# Sheet1.net
KiCad netlist of a schematic drawn in Altium Designer
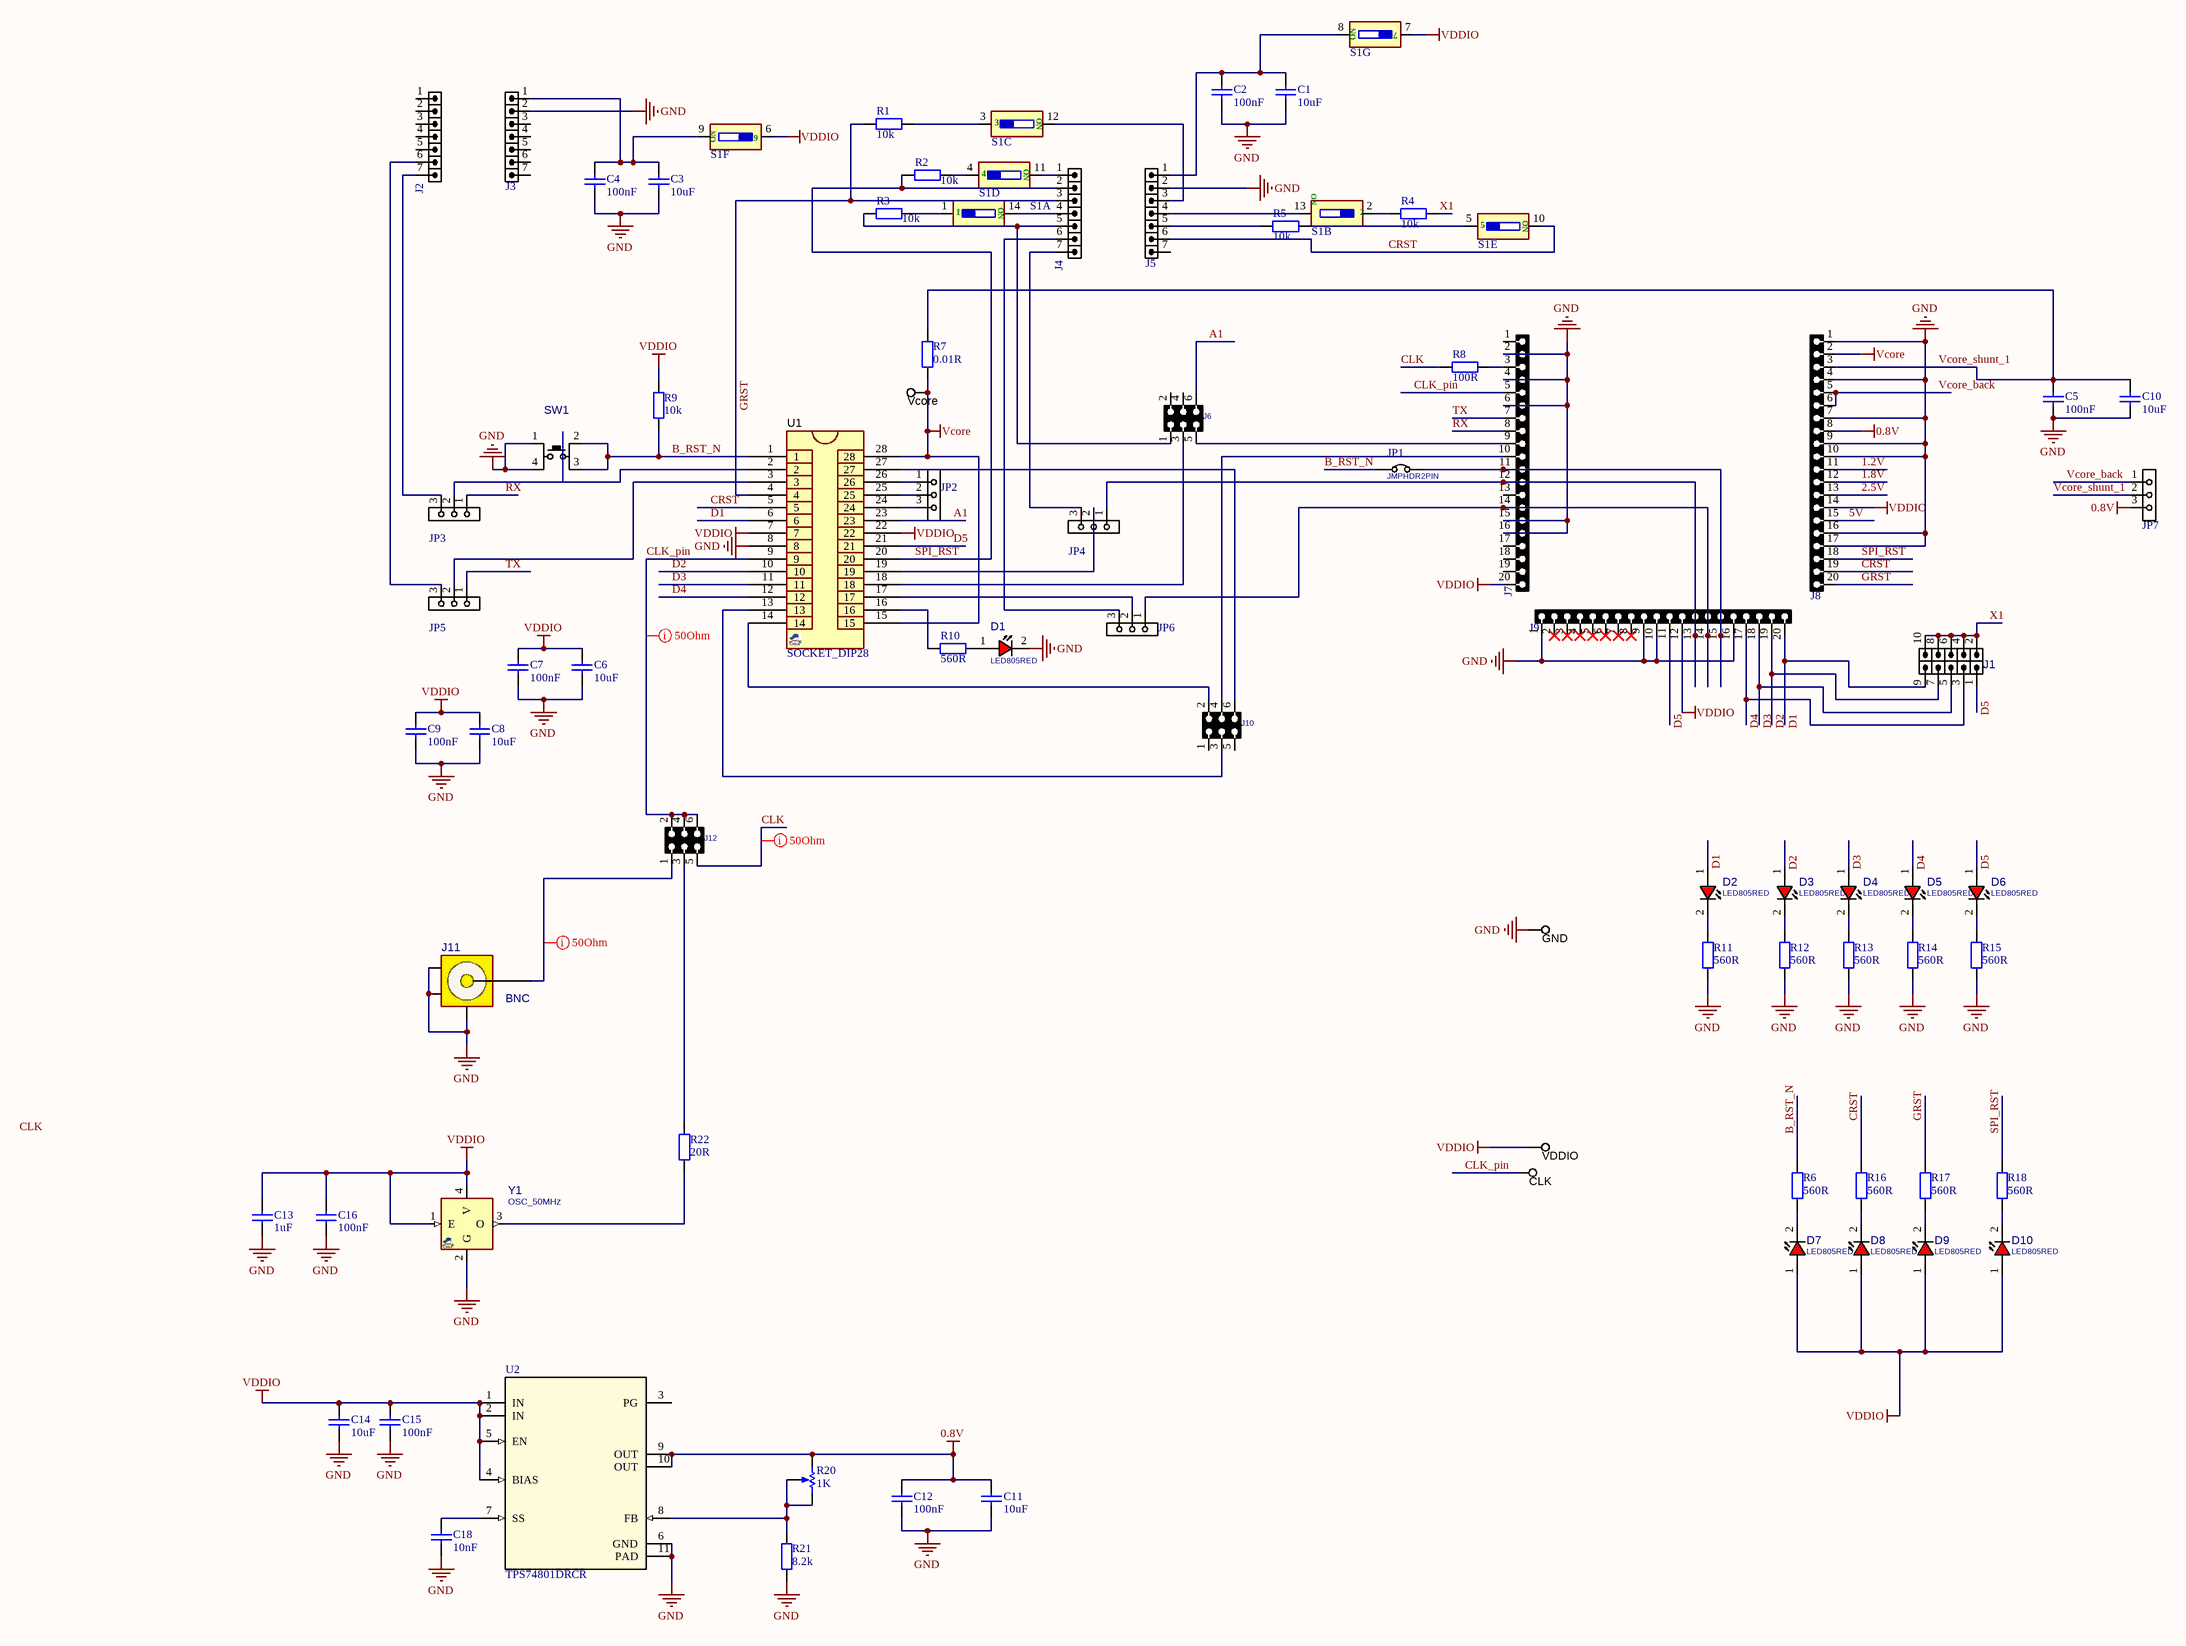
[diagram p0: Sheet1.SchDoc]

(export (version "E")
  (design (tool "Eeschema 10.0.6"))
  (components
    (comp (ref "C1")
      (value "10uF")
      (footprint "C1210")
      (description "smd capacitor 1206")
      (libsource (lib "mohamad_lib") (part "cap_SMD"))
    )
    (comp (ref "C2")
      (value "100nF")
      (footprint "C0805")
      (description "smd capacitor 1206")
      (libsource (lib "mohamad_lib") (part "cap_SMD"))
    )
    (comp (ref "C3")
      (value "10uF")
      (footprint "C1210")
      (description "smd capacitor 1206")
      (libsource (lib "mohamad_lib") (part "cap_SMD"))
    )
    (comp (ref "C4")
      (value "100nF")
      (footprint "C0805")
      (description "smd capacitor 1206")
      (libsource (lib "mohamad_lib") (part "cap_SMD"))
    )
    (comp (ref "C5")
      (value "100nF")
      (footprint "C0805")
      (description "smd capacitor 1206")
      (libsource (lib "mohamad_lib") (part "cap_SMD"))
    )
    (comp (ref "C6")
      (value "10uF")
      (footprint "C1210")
      (description "smd capacitor 1206")
      (libsource (lib "mohamad_lib") (part "cap_SMD"))
    )
    (comp (ref "C7")
      (value "100nF")
      (footprint "C0805")
      (description "smd capacitor 1206")
      (libsource (lib "mohamad_lib") (part "cap_SMD"))
    )
    (comp (ref "C8")
      (value "10uF")
      (footprint "C1210")
      (description "smd capacitor 1206")
      (libsource (lib "mohamad_lib") (part "cap_SMD"))
    )
    (comp (ref "C9")
      (value "100nF")
      (footprint "C0805")
      (description "smd capacitor 1206")
      (libsource (lib "mohamad_lib") (part "cap_SMD"))
    )
    (comp (ref "C10")
      (value "10uF")
      (footprint "C1210")
      (description "smd capacitor 1206")
      (libsource (lib "mohamad_lib") (part "cap_SMD"))
    )
    (comp (ref "C11")
      (value "10uF")
      (footprint "C1210")
      (description "smd capacitor 1206")
      (libsource (lib "mohamad_lib") (part "cap_SMD"))
    )
    (comp (ref "C12")
      (value "100nF")
      (footprint "C0805")
      (description "smd capacitor 1206")
      (libsource (lib "mohamad_lib") (part "cap_SMD"))
    )
    (comp (ref "C13")
      (value "1uF")
      (footprint "C0805")
      (description "smd capacitor 1206")
      (libsource (lib "mohamad_lib") (part "cap_SMD"))
    )
    (comp (ref "C14")
      (value "10uF")
      (footprint "C1210")
      (description "smd capacitor 1206")
      (libsource (lib "mohamad_lib") (part "cap_SMD"))
    )
    (comp (ref "C15")
      (value "100nF")
      (footprint "C0805")
      (description "smd capacitor 1206")
      (libsource (lib "mohamad_lib") (part "cap_SMD"))
    )
    (comp (ref "C16")
      (value "100nF")
      (footprint "C0805")
      (description "smd capacitor 1206")
      (libsource (lib "mohamad_lib") (part "cap_SMD"))
    )
    (comp (ref "C18")
      (value "10nF")
      (footprint "C0805")
      (description "smd capacitor 1206")
      (libsource (lib "mohamad_lib") (part "cap_SMD"))
    )
    (comp (ref "CLK")
      (value "TESTPOINT_BIG_BLK1")
      (footprint "TPTHD_C_BLK1")
      (description "TEST POINT")
      (fields (field (name "MANF") "MANF") (field (name "MANF_P#") "MANF_P#"))
      (libsource (lib "boorghani") (part "TESTPOINT_BIG_BLK1"))
    )
    (comp (ref "D1")
      (value "LED805RED")
      (footprint "LED0805RED")
      (description "LED, SMD, 0805, RED")
      (fields (field (name "MANF") "MANF") (field (name "MANF_P#") "MANF_PART#"))
      (libsource (lib "boorghani") (part "LED_SMD_0805_RED"))
    )
    (comp (ref "D2")
      (value "LED805RED")
      (footprint "LED0805RED")
      (description "LED, SMD, 0805, RED")
      (fields (field (name "MANF") "MANF") (field (name "MANF_P#") "MANF_PART#"))
      (libsource (lib "boorghani") (part "LED_SMD_0805_RED"))
    )
    (comp (ref "D3")
      (value "LED805RED")
      (footprint "LED0805RED")
      (description "LED, SMD, 0805, RED")
      (fields (field (name "MANF") "MANF") (field (name "MANF_P#") "MANF_PART#"))
      (libsource (lib "boorghani") (part "LED_SMD_0805_RED"))
    )
    (comp (ref "D4")
      (value "LED805RED")
      (footprint "LED0805RED")
      (description "LED, SMD, 0805, RED")
      (fields (field (name "MANF") "MANF") (field (name "MANF_P#") "MANF_PART#"))
      (libsource (lib "boorghani") (part "LED_SMD_0805_RED"))
    )
    (comp (ref "D5")
      (value "LED805RED")
      (footprint "LED0805RED")
      (description "LED, SMD, 0805, RED")
      (fields (field (name "MANF") "MANF") (field (name "MANF_P#") "MANF_PART#"))
      (libsource (lib "boorghani") (part "LED_SMD_0805_RED"))
    )
    (comp (ref "D6")
      (value "LED805RED")
      (footprint "LED0805RED")
      (description "LED, SMD, 0805, RED")
      (fields (field (name "MANF") "MANF") (field (name "MANF_P#") "MANF_PART#"))
      (libsource (lib "boorghani") (part "LED_SMD_0805_RED"))
    )
    (comp (ref "D7")
      (value "LED805RED")
      (footprint "LED0805RED")
      (description "LED, SMD, 0805, RED")
      (fields (field (name "MANF") "MANF") (field (name "MANF_P#") "MANF_PART#"))
      (libsource (lib "boorghani") (part "LED_SMD_0805_RED"))
    )
    (comp (ref "D8")
      (value "LED805RED")
      (footprint "LED0805RED")
      (description "LED, SMD, 0805, RED")
      (fields (field (name "MANF") "MANF") (field (name "MANF_P#") "MANF_PART#"))
      (libsource (lib "boorghani") (part "LED_SMD_0805_RED"))
    )
    (comp (ref "D9")
      (value "LED805RED")
      (footprint "LED0805RED")
      (description "LED, SMD, 0805, RED")
      (fields (field (name "MANF") "MANF") (field (name "MANF_P#") "MANF_PART#"))
      (libsource (lib "boorghani") (part "LED_SMD_0805_RED"))
    )
    (comp (ref "D10")
      (value "LED805RED")
      (footprint "LED0805RED")
      (description "LED, SMD, 0805, RED")
      (fields (field (name "MANF") "MANF") (field (name "MANF_P#") "MANF_PART#"))
      (libsource (lib "boorghani") (part "LED_SMD_0805_RED"))
    )
    (comp (ref "GND")
      (value "TESTPOINT_BIG_BLK1")
      (footprint "TPTHD_C_BLK1")
      (description "TEST POINT")
      (fields (field (name "MANF") "MANF") (field (name "MANF_P#") "MANF_P#"))
      (libsource (lib "boorghani") (part "TESTPOINT_BIG_BLK1"))
    )
    (comp (ref "J1")
      (value "HDRM_2X5")
      (footprint "HDR_M_2X5")
      (description "CONN, HEADER, Male, pitch: 2.54mm, 10POS")
      (libsource (lib "boorghani") (part "HDR_M_2X5"))
    )
    (comp (ref "J2")
      (value "HDR1X7")
      (footprint "HDR_M_1X7")
      (description "CONN, HEADER, Male, pitch: 2.54mm, 7POS")
      (libsource (lib "") (part "HDR_M_1X7_1"))
    )
    (comp (ref "J3")
      (value "HDR1X7")
      (footprint "HDR_M_1X7")
      (description "CONN, HEADER, Male, pitch: 2.54mm, 7POS")
      (libsource (lib "boorghani") (part "HDR_M_1X7"))
    )
    (comp (ref "J4")
      (value "HDR1X7")
      (footprint "HDR_M_1X7")
      (description "CONN, HEADER, Male, pitch: 2.54mm, 7POS")
      (libsource (lib "") (part "HDR_M_1X7_1"))
    )
    (comp (ref "J5")
      (value "HDR1X7")
      (footprint "HDR_M_1X7")
      (description "CONN, HEADER, Male, pitch: 2.54mm, 7POS")
      (libsource (lib "boorghani") (part "HDR_M_1X7"))
    )
    (comp (ref "J6")
      (value "HDRF_2X3")
      (footprint "HDR_F_2X3")
      (description "CONN, HEADER, Female, pitch: 2.54mm, 6POS")
      (fields (field (name "MANF_P#") "MANF_PART#") (field (name "MANF") "MANF"))
      (libsource (lib "boorghani") (part "HDR_F_2X3"))
    )
    (comp (ref "J7")
      (value "HDRF20")
      (footprint "HDR_F_1X20")
      (description "CONN, HEADER, Female, pitch: 2.54mm, 20POS")
      (libsource (lib "boorghani") (part "HDR_F_1X20"))
    )
    (comp (ref "J8")
      (value "HDRF20")
      (footprint "HDR_F_1X20")
      (description "CONN, HEADER, Female, pitch: 2.54mm, 20POS")
      (libsource (lib "boorghani") (part "HDR_F_1X20"))
    )
    (comp (ref "J9")
      (value "HDRF20")
      (footprint "HDR_F_1X20")
      (description "CONN, HEADER, Female, pitch: 2.54mm, 20POS")
      (libsource (lib "boorghani") (part "HDR_F_1X20"))
    )
    (comp (ref "J10")
      (value "HDRF_2X3")
      (footprint "HDR_F_2X3")
      (description "CONN, HEADER, Female, pitch: 2.54mm, 6POS")
      (fields (field (name "MANF_P#") "MANF_PART#") (field (name "MANF") "MANF"))
      (libsource (lib "boorghani") (part "HDR_F_2X3"))
    )
    (comp (ref "J11")
      (value "BNC")
      (footprint "MCX5.08-V5")
      (description "CONN, RF, BNC, STRAIGHT")
      (fields (field (name "MANF_P#") "5413515-9") (field (name "MANF") "TE"))
      (libsource (lib "boorghani") (part "CONN_RF_BNC_RA"))
    )
    (comp (ref "J12")
      (value "HDRF_2X3")
      (footprint "HDR_F_2X3")
      (description "CONN, HEADER, Female, pitch: 2.54mm, 6POS")
      (fields (field (name "MANF_P#") "MANF_PART#") (field (name "MANF") "MANF"))
      (libsource (lib "boorghani") (part "HDR_F_2X3"))
    )
    (comp (ref "JP1")
      (value "JMPHDR2PIN")
      (footprint "JP_2_BLK")
      (description "JUMPER, HEADER 2PIN")
      (fields (field (name "MANF") "MANF") (field (name "MANF_P#") "MANF_P#"))
      (libsource (lib "boorghani") (part "JUMPER_HDR_2P"))
    )
    (comp (ref "JP2")
      (value "JMPHDR3PIN")
      (footprint "JP_3")
      (description "JUMPER, HEADER 3PIN")
      (fields (field (name "MANF") "MANF") (field (name "MANF_P#") "MANF_P#"))
      (libsource (lib "") (part "JUMPER_HDR_3P_1"))
    )
    (comp (ref "JP3")
      (value "JMPHDR3PIN")
      (footprint "JP_3")
      (description "JUMPER, HEADER 3PIN")
      (fields (field (name "MANF") "MANF") (field (name "MANF_P#") "MANF_P#"))
      (libsource (lib "boorghani") (part "JUMPER_HDR_3P"))
    )
    (comp (ref "JP4")
      (value "JMPHDR3PIN")
      (footprint "JP_3")
      (description "JUMPER, HEADER 3PIN")
      (fields (field (name "MANF") "MANF") (field (name "MANF_P#") "MANF_P#"))
      (libsource (lib "boorghani") (part "JUMPER_HDR_3P"))
    )
    (comp (ref "JP5")
      (value "JMPHDR3PIN")
      (footprint "JP_3")
      (description "JUMPER, HEADER 3PIN")
      (fields (field (name "MANF") "MANF") (field (name "MANF_P#") "MANF_P#"))
      (libsource (lib "boorghani") (part "JUMPER_HDR_3P"))
    )
    (comp (ref "JP6")
      (value "JMPHDR3PIN")
      (footprint "JP_3")
      (description "JUMPER, HEADER 3PIN")
      (fields (field (name "MANF") "MANF") (field (name "MANF_P#") "MANF_P#"))
      (libsource (lib "boorghani") (part "JUMPER_HDR_3P"))
    )
    (comp (ref "JP7")
      (value "JMPHDR3PIN")
      (footprint "JP_3")
      (description "JUMPER, HEADER 3PIN")
      (fields (field (name "MANF") "MANF") (field (name "MANF_P#") "MANF_P#"))
      (libsource (lib "") (part "JUMPER_HDR_3P_1"))
    )
    (comp (ref "R1")
      (value "10k")
      (footprint "R0805")
      (description "resistors_axial_smd")
      (libsource (lib "") (part "Res_SMD_2"))
    )
    (comp (ref "R2")
      (value "10k")
      (footprint "R0805")
      (description "resistors_axial_smd")
      (libsource (lib "") (part "Res_SMD_2"))
    )
    (comp (ref "R3")
      (value "10k")
      (footprint "R0805")
      (description "resistors_axial_smd")
      (libsource (lib "") (part "Res_SMD_2"))
    )
    (comp (ref "R4")
      (value "10k")
      (footprint "R0805")
      (description "resistors_axial_smd")
      (libsource (lib "") (part "Res_SMD_2"))
    )
    (comp (ref "R5")
      (value "10k")
      (footprint "R0805")
      (description "resistors_axial_smd")
      (libsource (lib "") (part "Res_SMD_2"))
    )
    (comp (ref "R6")
      (value "560R")
      (footprint "R0805")
      (description "resistors_axial_smd")
      (libsource (lib "") (part "Res_SMD_1"))
    )
    (comp (ref "R7")
      (value "0.01R")
      (footprint "R1206")
      (description "resistors_axial_smd")
      (libsource (lib "mohamad_lib") (part "Res_SMD"))
    )
    (comp (ref "R8")
      (value "100R")
      (footprint "R0805")
      (description "resistors_axial_smd")
      (libsource (lib "") (part "Res_SMD_2"))
    )
    (comp (ref "R9")
      (value "10k")
      (footprint "R0805")
      (description "resistors_axial_smd")
      (libsource (lib "mohamad_lib") (part "Res_SMD"))
    )
    (comp (ref "R10")
      (value "560R")
      (footprint "R0805")
      (description "resistors_axial_smd")
      (libsource (lib "") (part "Res_SMD_2"))
    )
    (comp (ref "R11")
      (value "560R")
      (footprint "R0805")
      (description "resistors_axial_smd")
      (libsource (lib "mohamad_lib") (part "Res_SMD"))
    )
    (comp (ref "R12")
      (value "560R")
      (footprint "R0805")
      (description "resistors_axial_smd")
      (libsource (lib "mohamad_lib") (part "Res_SMD"))
    )
    (comp (ref "R13")
      (value "560R")
      (footprint "R0805")
      (description "resistors_axial_smd")
      (libsource (lib "mohamad_lib") (part "Res_SMD"))
    )
    (comp (ref "R14")
      (value "560R")
      (footprint "R0805")
      (description "resistors_axial_smd")
      (libsource (lib "mohamad_lib") (part "Res_SMD"))
    )
    (comp (ref "R15")
      (value "560R")
      (footprint "R0805")
      (description "resistors_axial_smd")
      (libsource (lib "mohamad_lib") (part "Res_SMD"))
    )
    (comp (ref "R16")
      (value "560R")
      (footprint "R0805")
      (description "resistors_axial_smd")
      (libsource (lib "") (part "Res_SMD_1"))
    )
    (comp (ref "R17")
      (value "560R")
      (footprint "R0805")
      (description "resistors_axial_smd")
      (libsource (lib "") (part "Res_SMD_1"))
    )
    (comp (ref "R18")
      (value "560R")
      (footprint "R0805")
      (description "resistors_axial_smd")
      (libsource (lib "") (part "Res_SMD_1"))
    )
    (comp (ref "R20")
      (value "1K")
      (footprint "Pot-a")
      (description "potansiometer")
      (libsource (lib "mohamad_lib") (part "ResPot"))
    )
    (comp (ref "R21")
      (value "8.2k")
      (footprint "R0805")
      (description "resistors_axial_smd")
      (libsource (lib "mohamad_lib") (part "Res_SMD"))
    )
    (comp (ref "R22")
      (value "20R")
      (footprint "R0805")
      (description "resistors_axial_smd")
      (libsource (lib "mohamad_lib") (part "Res_SMD"))
    )
    (comp (ref "S1")
      (value "DIPSW7")
      (footprint "DIPSW254S_7")
      (description "SWITCH, DIP, 7P, THD")
      (fields (field (name "MANF") "MANF") (field (name "MANF_P#") "MANF_P#"))
      (libsource (lib "boorghani") (part "DIPSW254S_7P"))
    )
    (comp (ref "SW1")
      (value "PUSHBUTTON")
      (footprint "SWPBS_SPDT_5X5X1")
      (description "SWITCH, PUSH BUTTON, TACTILE, SMD, SPDT, 5.0X5.0X1.5MM")
      (fields (field (name "MANF") "ALPS") (field (name "MANF_P#") "SKQGAFE010"))
      (libsource (lib "boorghani") (part "SWPBS_SPDT_5X5X1_SKQGAFE010"))
    )
    (comp (ref "U1")
      (value "SOCKET_DIP28")
      (footprint "DIP28_sckt")
      (description "SOCKET, IC DIP,")
      (libsource (lib "boorghani") (part "SOCKET_IC_DIP_28"))
    )
    (comp (ref "U2")
      (value "TPS74801DRCR")
      (footprint "DRC0010A")
      (fields
        (field (name "ALTERNATE_PARTNUMBER") "TPS74801DRCT")
        (field (name "MANUFACTURER") "Texas Instruments")
        (field (name "COPYRIGHT") "Copyright (C) 2026 Ultra Librarian. All rights reserved.")
      )
      (libsource (lib "TPS74801DRCR") (part "TPS74801DRCR"))
    )
    (comp (ref "Vcore")
      (value "TESTPOINT_BIG_BLK1")
      (footprint "TPTHD_C_BLK1")
      (description "TEST POINT")
      (fields (field (name "MANF") "MANF") (field (name "MANF_P#") "MANF_P#"))
      (libsource (lib "boorghani") (part "TESTPOINT_BIG_BLK1"))
    )
    (comp (ref "VDDIO")
      (value "TESTPOINT_BIG_BLK1")
      (footprint "TPTHD_C_BLK1")
      (description "TEST POINT")
      (fields (field (name "MANF") "MANF") (field (name "MANF_P#") "MANF_P#"))
      (libsource (lib "boorghani") (part "TESTPOINT_BIG_BLK1"))
    )
    (comp (ref "Y1")
      (value "OSC_50MHz")
      (footprint "XTL_4_3225GEN")
      (description "CLOCK OSCILLATOR, 50MHz, 10PPM, 3225")
      (fields (field (name "MANF") "ECS") (field (name "MANF_P#") "ECS-3225S33-500-FN-TR"))
      (libsource (lib "boorghani") (part "OSC_4_50MHz_3225E"))
    )
  )
  (nets
    (net (code "1") (name "/1.2V") (class "Default")
      (node (ref "J8") (pin "11") (pinfunction "11_11") (pintype "passive"))
    )
    (net (code "2") (name "/1.8V") (class "Default")
      (node (ref "J8") (pin "12") (pinfunction "12_12") (pintype "passive"))
    )
    (net (code "3") (name "/2.5V") (class "Default")
      (node (ref "J8") (pin "13") (pinfunction "13_13") (pintype "passive"))
    )
    (net (code "4") (name "/5V") (class "Default")
      (node (ref "J8") (pin "15") (pinfunction "15_15") (pintype "passive"))
    )
    (net (code "5") (name "/A1") (class "Default")
      (node (ref "J6") (pin "6") (pinfunction "6_6") (pintype "passive"))
      (node (ref "U1") (pin "23") (pinfunction "23_23") (pintype "passive"))
    )
    (net (code "6") (name "/B_RST_N") (class "Default")
      (node (ref "JP1") (pin "1") (pinfunction "1_1") (pintype "passive"))
      (node (ref "R6") (pin "1") (pinfunction "1_1") (pintype "passive"))
      (node (ref "R9") (pin "1") (pinfunction "1_1") (pintype "passive"))
      (node (ref "SW1") (pin "2") (pinfunction "P3_2") (pintype "passive"))
      (node (ref "SW1") (pin "3") (pinfunction "P4_3") (pintype "passive"))
      (node (ref "U1") (pin "1") (pinfunction "1_1") (pintype "passive"))
    )
    (net (code "7") (name "/CLK") (class "Default")
      (node (ref "J12") (pin "5") (pinfunction "5_5") (pintype "passive"))
      (node (ref "R8") (pin "2") (pinfunction "2_2") (pintype "passive"))
    )
    (net (code "8") (name "/CLK_pin") (class "Default")
      (node (ref "CLK") (pin "1") (pinfunction "1_1") (pintype "passive"))
      (node (ref "J12") (pin "2") (pinfunction "2_2") (pintype "passive"))
      (node (ref "J12") (pin "4") (pinfunction "4_4") (pintype "passive"))
      (node (ref "J12") (pin "6") (pinfunction "6_6") (pintype "passive"))
      (node (ref "J7") (pin "5") (pinfunction "5_5") (pintype "passive"))
      (node (ref "U1") (pin "9") (pinfunction "9_9") (pintype "passive"))
    )
    (net (code "9") (name "/CRST") (class "Default")
      (node (ref "J5") (pin "6") (pinfunction "6_6") (pintype "passive"))
      (node (ref "J8") (pin "19") (pinfunction "19_19") (pintype "passive"))
      (node (ref "R16") (pin "1") (pinfunction "1_1") (pintype "passive"))
      (node (ref "S1") (pin "10") (pinfunction "B5_10") (pintype "passive"))
      (node (ref "U1") (pin "5") (pinfunction "5_5") (pintype "passive"))
    )
    (net (code "10") (name "/D1") (class "Default")
      (node (ref "D2") (pin "1") (pinfunction "ANODE_1") (pintype "passive"))
      (node (ref "J1") (pin "9") (pinfunction "9_9") (pintype "passive"))
      (node (ref "J9") (pin "20") (pinfunction "20_20") (pintype "passive"))
      (node (ref "U1") (pin "6") (pinfunction "6_6") (pintype "passive"))
    )
    (net (code "11") (name "/D2") (class "Default")
      (node (ref "D3") (pin "1") (pinfunction "ANODE_1") (pintype "passive"))
      (node (ref "J1") (pin "7") (pinfunction "7_7") (pintype "passive"))
      (node (ref "J9") (pin "19") (pinfunction "19_19") (pintype "passive"))
      (node (ref "U1") (pin "10") (pinfunction "10_10") (pintype "passive"))
    )
    (net (code "12") (name "/D3") (class "Default")
      (node (ref "D4") (pin "1") (pinfunction "ANODE_1") (pintype "passive"))
      (node (ref "J1") (pin "5") (pinfunction "5_5") (pintype "passive"))
      (node (ref "J9") (pin "18") (pinfunction "18_18") (pintype "passive"))
      (node (ref "U1") (pin "11") (pinfunction "11_11") (pintype "passive"))
    )
    (net (code "13") (name "/D4") (class "Default")
      (node (ref "D5") (pin "1") (pinfunction "ANODE_1") (pintype "passive"))
      (node (ref "J1") (pin "3") (pinfunction "3_3") (pintype "passive"))
      (node (ref "J9") (pin "17") (pinfunction "17_17") (pintype "passive"))
      (node (ref "U1") (pin "12") (pinfunction "12_12") (pintype "passive"))
    )
    (net (code "14") (name "/D5") (class "Default")
      (node (ref "D6") (pin "1") (pinfunction "ANODE_1") (pintype "passive"))
      (node (ref "J1") (pin "1") (pinfunction "1_1") (pintype "passive"))
      (node (ref "J9") (pin "11") (pinfunction "11_11") (pintype "passive"))
      (node (ref "U1") (pin "21") (pinfunction "21_21") (pintype "passive"))
    )
    (net (code "15") (name "/GRST") (class "Default")
      (node (ref "J4") (pin "3") (pinfunction "3_3") (pintype "passive"))
      (node (ref "J8") (pin "20") (pinfunction "20_20") (pintype "passive"))
      (node (ref "R1") (pin "2") (pinfunction "2_2") (pintype "passive"))
      (node (ref "R17") (pin "1") (pinfunction "1_1") (pintype "passive"))
      (node (ref "U1") (pin "4") (pinfunction "4_4") (pintype "passive"))
    )
    (net (code "16") (name "/RX") (class "Default")
      (node (ref "J7") (pin "8") (pinfunction "8_8") (pintype "passive"))
      (node (ref "JP3") (pin "1") (pinfunction "1_1") (pintype "passive"))
    )
    (net (code "17") (name "/SPI_RST") (class "Default")
      (node (ref "J4") (pin "2") (pinfunction "2_2") (pintype "passive"))
      (node (ref "J8") (pin "18") (pinfunction "18_18") (pintype "passive"))
      (node (ref "R18") (pin "1") (pinfunction "1_1") (pintype "passive"))
      (node (ref "R2") (pin "2") (pinfunction "2_2") (pintype "passive"))
      (node (ref "U1") (pin "20") (pinfunction "20_20") (pintype "passive"))
    )
    (net (code "18") (name "/TX") (class "Default")
      (node (ref "J7") (pin "7") (pinfunction "7_7") (pintype "passive"))
      (node (ref "JP5") (pin "1") (pinfunction "1_1") (pintype "passive"))
    )
    (net (code "19") (name "/Vcore_back") (class "Default")
      (node (ref "J8") (pin "5") (pinfunction "5_5") (pintype "passive"))
      (node (ref "J8") (pin "6") (pinfunction "6_6") (pintype "passive"))
      (node (ref "JP7") (pin "1") (pinfunction "1_1") (pintype "passive"))
    )
    (net (code "20") (name "/Vcore_shunt_1") (class "Default")
      (node (ref "C10") (pin "2") (pinfunction "2_2") (pintype "passive"))
      (node (ref "C5") (pin "2") (pinfunction "2_2") (pintype "passive"))
      (node (ref "J8") (pin "3") (pinfunction "3_3") (pintype "passive"))
      (node (ref "JP7") (pin "2") (pinfunction "2_2") (pintype "passive"))
      (node (ref "R7") (pin "2") (pinfunction "2_2") (pintype "passive"))
    )
    (net (code "21") (name "/X1") (class "Default")
      (node (ref "J1") (pin "10") (pinfunction "10_10") (pintype "passive"))
      (node (ref "J1") (pin "2") (pinfunction "2_2") (pintype "passive"))
      (node (ref "J1") (pin "4") (pinfunction "4_4") (pintype "passive"))
      (node (ref "J1") (pin "6") (pinfunction "6_6") (pintype "passive"))
      (node (ref "J1") (pin "8") (pinfunction "8_8") (pintype "passive"))
      (node (ref "R4") (pin "1") (pinfunction "1_1") (pintype "passive"))
    )
    (net (code "22") (name "0.8V") (class "Default")
      (node (ref "C11") (pin "2") (pinfunction "2_2") (pintype "passive"))
      (node (ref "C12") (pin "1") (pinfunction "1_1") (pintype "passive"))
      (node (ref "J8") (pin "8") (pinfunction "8_8") (pintype "passive"))
      (node (ref "JP7") (pin "3") (pinfunction "3_3") (pintype "passive"))
      (node (ref "R20") (pin "1") (pinfunction "TOP_1") (pintype "passive"))
      (node (ref "U2") (pin "10") (pinfunction "OUT_10") (pintype "power_in"))
      (node (ref "U2") (pin "9") (pinfunction "OUT_9") (pintype "power_in"))
    )
    (net (code "23") (name "GND") (class "Default")
      (node (ref "C1") (pin "1") (pinfunction "1_1") (pintype "passive"))
      (node (ref "C10") (pin "1") (pinfunction "1_1") (pintype "passive"))
      (node (ref "C11") (pin "1") (pinfunction "1_1") (pintype "passive"))
      (node (ref "C12") (pin "2") (pinfunction "2_2") (pintype "passive"))
      (node (ref "C13") (pin "2") (pinfunction "2_2") (pintype "passive"))
      (node (ref "C14") (pin "1") (pinfunction "1_1") (pintype "passive"))
      (node (ref "C15") (pin "2") (pinfunction "2_2") (pintype "passive"))
      (node (ref "C16") (pin "2") (pinfunction "2_2") (pintype "passive"))
      (node (ref "C18") (pin "2") (pinfunction "2_2") (pintype "passive"))
      (node (ref "C2") (pin "2") (pinfunction "2_2") (pintype "passive"))
      (node (ref "C3") (pin "1") (pinfunction "1_1") (pintype "passive"))
      (node (ref "C4") (pin "2") (pinfunction "2_2") (pintype "passive"))
      (node (ref "C5") (pin "1") (pinfunction "1_1") (pintype "passive"))
      (node (ref "C6") (pin "1") (pinfunction "1_1") (pintype "passive"))
      (node (ref "C7") (pin "2") (pinfunction "2_2") (pintype "passive"))
      (node (ref "C8") (pin "1") (pinfunction "1_1") (pintype "passive"))
      (node (ref "C9") (pin "2") (pinfunction "2_2") (pintype "passive"))
      (node (ref "D1") (pin "2") (pinfunction "CATHODE_2") (pintype "passive"))
      (node (ref "GND") (pin "1") (pinfunction "1_1") (pintype "passive"))
      (node (ref "J11") (pin "2") (pinfunction "GND_2") (pintype "passive"))
      (node (ref "J11") (pin "MH1") (pinfunction "MH1_MH1") (pintype "passive"))
      (node (ref "J11") (pin "MH2") (pinfunction "MH2_MH2") (pintype "passive"))
      (node (ref "J3") (pin "2") (pinfunction "2_2") (pintype "passive"))
      (node (ref "J5") (pin "2") (pinfunction "2_2") (pintype "passive"))
      (node (ref "J7") (pin "15") (pinfunction "15_15") (pintype "passive"))
      (node (ref "J7") (pin "16") (pinfunction "16_16") (pintype "passive"))
      (node (ref "J7") (pin "2") (pinfunction "2_2") (pintype "passive"))
      (node (ref "J7") (pin "4") (pinfunction "4_4") (pintype "passive"))
      (node (ref "J7") (pin "6") (pinfunction "6_6") (pintype "passive"))
      (node (ref "J8") (pin "1") (pinfunction "1_1") (pintype "passive"))
      (node (ref "J8") (pin "10") (pinfunction "10_10") (pintype "passive"))
      (node (ref "J8") (pin "16") (pinfunction "16_16") (pintype "passive"))
      (node (ref "J8") (pin "17") (pinfunction "17_17") (pintype "passive"))
      (node (ref "J8") (pin "4") (pinfunction "4_4") (pintype "passive"))
      (node (ref "J8") (pin "7") (pinfunction "7_7") (pintype "passive"))
      (node (ref "J8") (pin "9") (pinfunction "9_9") (pintype "passive"))
      (node (ref "J9") (pin "1") (pinfunction "1_1") (pintype "passive"))
      (node (ref "J9") (pin "10") (pinfunction "10_10") (pintype "passive"))
      (node (ref "J9") (pin "16") (pinfunction "16_16") (pintype "passive"))
      (node (ref "J9") (pin "9") (pinfunction "9_9") (pintype "passive"))
      (node (ref "R11") (pin "1") (pinfunction "1_1") (pintype "passive"))
      (node (ref "R12") (pin "1") (pinfunction "1_1") (pintype "passive"))
      (node (ref "R13") (pin "1") (pinfunction "1_1") (pintype "passive"))
      (node (ref "R14") (pin "1") (pinfunction "1_1") (pintype "passive"))
      (node (ref "R15") (pin "1") (pinfunction "1_1") (pintype "passive"))
      (node (ref "R21") (pin "1") (pinfunction "1_1") (pintype "passive"))
      (node (ref "SW1") (pin "1") (pinfunction "P1_1") (pintype "passive"))
      (node (ref "SW1") (pin "4") (pinfunction "P2_4") (pintype "passive"))
      (node (ref "U1") (pin "8") (pinfunction "8_8") (pintype "passive"))
      (node (ref "U2") (pin "11") (pinfunction "PAD_11") (pintype "power_in"))
      (node (ref "U2") (pin "6") (pinfunction "GND_6") (pintype "power_in"))
      (node (ref "Y1") (pin "2") (pinfunction "G_2") (pintype "power_in"))
    )
    (net (code "24") (name "Net-(D1-ANODE)") (class "Default")
      (node (ref "D1") (pin "1") (pinfunction "ANODE_1") (pintype "passive"))
      (node (ref "R10") (pin "1") (pinfunction "1_1") (pintype "passive"))
    )
    (net (code "25") (name "Net-(D2-CATHODE)") (class "Default")
      (node (ref "D2") (pin "2") (pinfunction "CATHODE_2") (pintype "passive"))
      (node (ref "R11") (pin "2") (pinfunction "2_2") (pintype "passive"))
    )
    (net (code "26") (name "Net-(D3-CATHODE)") (class "Default")
      (node (ref "D3") (pin "2") (pinfunction "CATHODE_2") (pintype "passive"))
      (node (ref "R12") (pin "2") (pinfunction "2_2") (pintype "passive"))
    )
    (net (code "27") (name "Net-(D4-CATHODE)") (class "Default")
      (node (ref "D4") (pin "2") (pinfunction "CATHODE_2") (pintype "passive"))
      (node (ref "R13") (pin "2") (pinfunction "2_2") (pintype "passive"))
    )
    (net (code "28") (name "Net-(D5-CATHODE)") (class "Default")
      (node (ref "D5") (pin "2") (pinfunction "CATHODE_2") (pintype "passive"))
      (node (ref "R14") (pin "2") (pinfunction "2_2") (pintype "passive"))
    )
    (net (code "29") (name "Net-(D6-CATHODE)") (class "Default")
      (node (ref "D6") (pin "2") (pinfunction "CATHODE_2") (pintype "passive"))
      (node (ref "R15") (pin "2") (pinfunction "2_2") (pintype "passive"))
    )
    (net (code "30") (name "Net-(D7-CATHODE)") (class "Default")
      (node (ref "D7") (pin "2") (pinfunction "CATHODE_2") (pintype "passive"))
      (node (ref "R6") (pin "2") (pinfunction "2_2") (pintype "passive"))
    )
    (net (code "31") (name "Net-(D8-CATHODE)") (class "Default")
      (node (ref "D8") (pin "2") (pinfunction "CATHODE_2") (pintype "passive"))
      (node (ref "R16") (pin "2") (pinfunction "2_2") (pintype "passive"))
    )
    (net (code "32") (name "Net-(D9-CATHODE)") (class "Default")
      (node (ref "D9") (pin "2") (pinfunction "CATHODE_2") (pintype "passive"))
      (node (ref "R17") (pin "2") (pinfunction "2_2") (pintype "passive"))
    )
    (net (code "33") (name "Net-(D10-CATHODE)") (class "Default")
      (node (ref "D10") (pin "2") (pinfunction "CATHODE_2") (pintype "passive"))
      (node (ref "R18") (pin "2") (pinfunction "2_2") (pintype "passive"))
    )
    (net (code "34") (name "Net-(J2-Pad6)") (class "Default")
      (node (ref "J2") (pin "6") (pinfunction "6_6") (pintype "passive"))
      (node (ref "JP5") (pin "3") (pinfunction "3_3") (pintype "passive"))
    )
    (net (code "35") (name "Net-(J2-Pad7)") (class "Default")
      (node (ref "J2") (pin "7") (pinfunction "7_7") (pintype "passive"))
      (node (ref "JP3") (pin "3") (pinfunction "3_3") (pintype "passive"))
    )
    (net (code "36") (name "Net-(J4-Pad5)") (class "Default")
      (node (ref "J4") (pin "5") (pinfunction "5_5") (pintype "passive"))
      (node (ref "J6") (pin "1") (pinfunction "1_1") (pintype "passive"))
      (node (ref "R3") (pin "2") (pinfunction "2_2") (pintype "passive"))
    )
    (net (code "37") (name "Net-(J4-Pad6)") (class "Default")
      (node (ref "J4") (pin "6") (pinfunction "6_6") (pintype "passive"))
      (node (ref "JP6") (pin "3") (pinfunction "3_3") (pintype "passive"))
    )
    (net (code "38") (name "Net-(J4-Pad7)") (class "Default")
      (node (ref "J4") (pin "7") (pinfunction "7_7") (pintype "passive"))
      (node (ref "JP4") (pin "3") (pinfunction "3_3") (pintype "passive"))
    )
    (net (code "39") (name "Net-(J5-Pad5)") (class "Default")
      (node (ref "J5") (pin "5") (pinfunction "5_5") (pintype "passive"))
      (node (ref "R5") (pin "2") (pinfunction "2_2") (pintype "passive"))
    )
    (net (code "40") (name "Net-(J6-Pad3)") (class "Default")
      (node (ref "J6") (pin "3") (pinfunction "3_3") (pintype "passive"))
      (node (ref "U1") (pin "18") (pinfunction "18_18") (pintype "passive"))
    )
    (net (code "41") (name "Net-(J6-Pad5)") (class "Default")
      (node (ref "J6") (pin "5") (pinfunction "5_5") (pintype "passive"))
      (node (ref "J7") (pin "9") (pinfunction "9_9") (pintype "passive"))
    )
    (net (code "42") (name "Net-(J7-Pad3)") (class "Default")
      (node (ref "J7") (pin "3") (pinfunction "3_3") (pintype "passive"))
      (node (ref "R8") (pin "1") (pinfunction "1_1") (pintype "passive"))
    )
    (net (code "43") (name "Net-(J7-Pad11)") (class "Default")
      (node (ref "J7") (pin "11") (pinfunction "11_11") (pintype "passive"))
      (node (ref "J9") (pin "15") (pinfunction "15_15") (pintype "passive"))
      (node (ref "JP1") (pin "2") (pinfunction "2_2") (pintype "passive"))
    )
    (net (code "44") (name "Net-(J7-Pad12)") (class "Default")
      (node (ref "J7") (pin "12") (pinfunction "12_12") (pintype "passive"))
      (node (ref "J9") (pin "13") (pinfunction "13_13") (pintype "passive"))
      (node (ref "JP4") (pin "1") (pinfunction "1_1") (pintype "passive"))
    )
    (net (code "45") (name "Net-(J7-Pad14)") (class "Default")
      (node (ref "J7") (pin "14") (pinfunction "14_14") (pintype "passive"))
      (node (ref "J9") (pin "14") (pinfunction "14_14") (pintype "passive"))
      (node (ref "JP6") (pin "1") (pinfunction "1_1") (pintype "passive"))
    )
    (net (code "46") (name "Net-(J10-Pad2)") (class "Default")
      (node (ref "J10") (pin "2") (pinfunction "2_2") (pintype "passive"))
      (node (ref "U1") (pin "14") (pinfunction "14_14") (pintype "passive"))
    )
    (net (code "47") (name "Net-(J10-Pad3)") (class "Default")
      (node (ref "J10") (pin "3") (pinfunction "3_3") (pintype "passive"))
      (node (ref "U1") (pin "13") (pinfunction "13_13") (pintype "passive"))
    )
    (net (code "48") (name "Net-(J10-Pad4)") (class "Default")
      (node (ref "J10") (pin "4") (pinfunction "4_4") (pintype "passive"))
      (node (ref "J7") (pin "10") (pinfunction "10_10") (pintype "passive"))
    )
    (net (code "49") (name "Net-(J10-Pad6)") (class "Default")
      (node (ref "J10") (pin "6") (pinfunction "6_6") (pintype "passive"))
      (node (ref "U1") (pin "27") (pinfunction "27_27") (pintype "passive"))
    )
    (net (code "50") (name "Net-(J11-SIG)") (class "Default")
      (node (ref "J11") (pin "1") (pinfunction "SIG_1") (pintype "passive"))
      (node (ref "J12") (pin "1") (pinfunction "1_1") (pintype "passive"))
    )
    (net (code "51") (name "Net-(J12-Pad3)") (class "Default")
      (node (ref "J12") (pin "3") (pinfunction "3_3") (pintype "passive"))
      (node (ref "R22") (pin "2") (pinfunction "2_2") (pintype "passive"))
    )
    (net (code "52") (name "Net-(JP2-Pad1)") (class "Default")
      (node (ref "JP2") (pin "1") (pinfunction "1_1") (pintype "passive"))
      (node (ref "U1") (pin "26") (pinfunction "26_26") (pintype "passive"))
    )
    (net (code "53") (name "Net-(JP2-Pad2)") (class "Default")
      (node (ref "JP2") (pin "2") (pinfunction "2_2") (pintype "passive"))
      (node (ref "U1") (pin "25") (pinfunction "25_25") (pintype "passive"))
    )
    (net (code "54") (name "Net-(JP2-Pad3)") (class "Default")
      (node (ref "JP2") (pin "3") (pinfunction "3_3") (pintype "passive"))
      (node (ref "U1") (pin "24") (pinfunction "24_24") (pintype "passive"))
    )
    (net (code "55") (name "Net-(JP3-Pad2)") (class "Default")
      (node (ref "JP3") (pin "2") (pinfunction "2_2") (pintype "passive"))
      (node (ref "U1") (pin "2") (pinfunction "2_2") (pintype "passive"))
    )
    (net (code "56") (name "Net-(JP4-Pad2)") (class "Default")
      (node (ref "JP4") (pin "2") (pinfunction "2_2") (pintype "passive"))
      (node (ref "U1") (pin "19") (pinfunction "19_19") (pintype "passive"))
    )
    (net (code "57") (name "Net-(JP5-Pad2)") (class "Default")
      (node (ref "JP5") (pin "2") (pinfunction "2_2") (pintype "passive"))
      (node (ref "U1") (pin "3") (pinfunction "3_3") (pintype "passive"))
    )
    (net (code "58") (name "Net-(JP6-Pad2)") (class "Default")
      (node (ref "JP6") (pin "2") (pinfunction "2_2") (pintype "passive"))
      (node (ref "U1") (pin "17") (pinfunction "17_17") (pintype "passive"))
    )
    (net (code "59") (name "Net-(R10-Pad2)") (class "Default")
      (node (ref "R10") (pin "2") (pinfunction "2_2") (pintype "passive"))
      (node (ref "U1") (pin "16") (pinfunction "16_16") (pintype "passive"))
    )
    (net (code "60") (name "Net-(R20-BOT)") (class "Default")
      (node (ref "R20") (pin "2") (pinfunction "TAP_2") (pintype "passive"))
      (node (ref "R20") (pin "3") (pinfunction "BOT_3") (pintype "passive"))
      (node (ref "R21") (pin "2") (pinfunction "2_2") (pintype "passive"))
      (node (ref "U2") (pin "8") (pinfunction "FB_8") (pintype "input"))
    )
    (net (code "61") (name "Net-(S1A-A1)") (class "Default")
      (node (ref "R3") (pin "1") (pinfunction "1_1") (pintype "passive"))
      (node (ref "S1") (pin "1") (pinfunction "A1_1") (pintype "passive"))
    )
    (net (code "62") (name "Net-(S1A-B1)") (class "Default")
      (node (ref "J4") (pin "4") (pinfunction "4_4") (pintype "passive"))
      (node (ref "S1") (pin "14") (pinfunction "B1_14") (pintype "passive"))
    )
    (net (code "63") (name "Net-(S1B-A2)") (class "Default")
      (node (ref "R4") (pin "2") (pinfunction "2_2") (pintype "passive"))
      (node (ref "S1") (pin "2") (pinfunction "A2_2") (pintype "passive"))
    )
    (net (code "64") (name "Net-(S1B-B2)") (class "Default")
      (node (ref "J5") (pin "4") (pinfunction "4_4") (pintype "passive"))
      (node (ref "S1") (pin "13") (pinfunction "B2_13") (pintype "passive"))
    )
    (net (code "65") (name "Net-(S1C-A3)") (class "Default")
      (node (ref "R1") (pin "1") (pinfunction "1_1") (pintype "passive"))
      (node (ref "S1") (pin "3") (pinfunction "A3_3") (pintype "passive"))
    )
    (net (code "66") (name "Net-(S1C-B3)") (class "Default")
      (node (ref "J5") (pin "3") (pinfunction "3_3") (pintype "passive"))
      (node (ref "S1") (pin "12") (pinfunction "B3_12") (pintype "passive"))
    )
    (net (code "67") (name "Net-(S1D-A4)") (class "Default")
      (node (ref "R2") (pin "1") (pinfunction "1_1") (pintype "passive"))
      (node (ref "S1") (pin "4") (pinfunction "A4_4") (pintype "passive"))
    )
    (net (code "68") (name "Net-(S1D-B4)") (class "Default")
      (node (ref "J4") (pin "1") (pinfunction "1_1") (pintype "passive"))
      (node (ref "S1") (pin "11") (pinfunction "B4_11") (pintype "passive"))
    )
    (net (code "69") (name "Net-(S1E-A5)") (class "Default")
      (node (ref "R5") (pin "1") (pinfunction "1_1") (pintype "passive"))
      (node (ref "S1") (pin "5") (pinfunction "A5_5") (pintype "passive"))
    )
    (net (code "70") (name "Net-(S1F-B6)") (class "Default")
      (node (ref "C3") (pin "2") (pinfunction "2_2") (pintype "passive"))
      (node (ref "C4") (pin "1") (pinfunction "1_1") (pintype "passive"))
      (node (ref "J3") (pin "1") (pinfunction "1_1") (pintype "passive"))
      (node (ref "S1") (pin "9") (pinfunction "B6_9") (pintype "passive"))
    )
    (net (code "71") (name "Net-(S1G-B7)") (class "Default")
      (node (ref "C1") (pin "2") (pinfunction "2_2") (pintype "passive"))
      (node (ref "C2") (pin "1") (pinfunction "1_1") (pintype "passive"))
      (node (ref "J5") (pin "1") (pinfunction "1_1") (pintype "passive"))
      (node (ref "S1") (pin "8") (pinfunction "B7_8") (pintype "passive"))
    )
    (net (code "72") (name "Net-(U2-SS)") (class "Default")
      (node (ref "C18") (pin "1") (pinfunction "1_1") (pintype "passive"))
      (node (ref "U2") (pin "7") (pinfunction "SS_7") (pintype "input"))
    )
    (net (code "73") (name "Net-(Y1-O)") (class "Default")
      (node (ref "R22") (pin "1") (pinfunction "1_1") (pintype "passive"))
      (node (ref "Y1") (pin "3") (pinfunction "O_3") (pintype "output"))
    )
    (net (code "74") (name "VDDIO") (class "Default")
      (node (ref "C13") (pin "1") (pinfunction "1_1") (pintype "passive"))
      (node (ref "C14") (pin "2") (pinfunction "2_2") (pintype "passive"))
      (node (ref "C15") (pin "1") (pinfunction "1_1") (pintype "passive"))
      (node (ref "C16") (pin "1") (pinfunction "1_1") (pintype "passive"))
      (node (ref "C6") (pin "2") (pinfunction "2_2") (pintype "passive"))
      (node (ref "C7") (pin "1") (pinfunction "1_1") (pintype "passive"))
      (node (ref "C8") (pin "2") (pinfunction "2_2") (pintype "passive"))
      (node (ref "C9") (pin "1") (pinfunction "1_1") (pintype "passive"))
      (node (ref "D10") (pin "1") (pinfunction "ANODE_1") (pintype "passive"))
      (node (ref "D7") (pin "1") (pinfunction "ANODE_1") (pintype "passive"))
      (node (ref "D8") (pin "1") (pinfunction "ANODE_1") (pintype "passive"))
      (node (ref "D9") (pin "1") (pinfunction "ANODE_1") (pintype "passive"))
      (node (ref "J7") (pin "20") (pinfunction "20_20") (pintype "passive"))
      (node (ref "J8") (pin "14") (pinfunction "14_14") (pintype "passive"))
      (node (ref "J9") (pin "12") (pinfunction "12_12") (pintype "passive"))
      (node (ref "R9") (pin "2") (pinfunction "2_2") (pintype "passive"))
      (node (ref "S1") (pin "6") (pinfunction "A6_6") (pintype "passive"))
      (node (ref "S1") (pin "7") (pinfunction "A7_7") (pintype "passive"))
      (node (ref "U1") (pin "22") (pinfunction "22_22") (pintype "passive"))
      (node (ref "U1") (pin "7") (pinfunction "7_7") (pintype "passive"))
      (node (ref "U2") (pin "1") (pinfunction "IN_1") (pintype "power_in"))
      (node (ref "U2") (pin "2") (pinfunction "IN_2") (pintype "power_in"))
      (node (ref "U2") (pin "4") (pinfunction "BIAS_4") (pintype "input"))
      (node (ref "U2") (pin "5") (pinfunction "EN_5") (pintype "input"))
      (node (ref "VDDIO") (pin "1") (pinfunction "1_1") (pintype "passive"))
      (node (ref "Y1") (pin "1") (pinfunction "E_1") (pintype "input"))
      (node (ref "Y1") (pin "4") (pinfunction "V_4") (pintype "power_in"))
    )
    (net (code "75") (name "Vcore") (class "Default")
      (node (ref "J8") (pin "2") (pinfunction "2_2") (pintype "passive"))
      (node (ref "R7") (pin "1") (pinfunction "1_1") (pintype "passive"))
      (node (ref "U1") (pin "15") (pinfunction "15_15") (pintype "passive"))
      (node (ref "U1") (pin "28") (pinfunction "28_28") (pintype "passive"))
      (node (ref "Vcore") (pin "1") (pinfunction "1_1") (pintype "passive"))
    )
    (net (code "76") (name "unconnected-(J2-Pad1)") (class "Default")
      (node (ref "J2") (pin "1") (pinfunction "1_1") (pintype "passive"))
    )
    (net (code "77") (name "unconnected-(J2-Pad2)") (class "Default")
      (node (ref "J2") (pin "2") (pinfunction "2_2") (pintype "passive"))
    )
    (net (code "78") (name "unconnected-(J2-Pad3)") (class "Default")
      (node (ref "J2") (pin "3") (pinfunction "3_3") (pintype "passive"))
    )
    (net (code "79") (name "unconnected-(J2-Pad4)") (class "Default")
      (node (ref "J2") (pin "4") (pinfunction "4_4") (pintype "passive"))
    )
    (net (code "80") (name "unconnected-(J2-Pad5)") (class "Default")
      (node (ref "J2") (pin "5") (pinfunction "5_5") (pintype "passive"))
    )
    (net (code "81") (name "unconnected-(J3-Pad3)") (class "Default")
      (node (ref "J3") (pin "3") (pinfunction "3_3") (pintype "passive"))
    )
    (net (code "82") (name "unconnected-(J3-Pad4)") (class "Default")
      (node (ref "J3") (pin "4") (pinfunction "4_4") (pintype "passive"))
    )
    (net (code "83") (name "unconnected-(J3-Pad5)") (class "Default")
      (node (ref "J3") (pin "5") (pinfunction "5_5") (pintype "passive"))
    )
    (net (code "84") (name "unconnected-(J3-Pad6)") (class "Default")
      (node (ref "J3") (pin "6") (pinfunction "6_6") (pintype "passive"))
    )
    (net (code "85") (name "unconnected-(J3-Pad7)") (class "Default")
      (node (ref "J3") (pin "7") (pinfunction "7_7") (pintype "passive"))
    )
    (net (code "86") (name "unconnected-(J5-Pad7)") (class "Default")
      (node (ref "J5") (pin "7") (pinfunction "7_7") (pintype "passive"))
    )
    (net (code "87") (name "unconnected-(J6-Pad2)") (class "Default")
      (node (ref "J6") (pin "2") (pinfunction "2_2") (pintype "passive"))
    )
    (net (code "88") (name "unconnected-(J6-Pad4)") (class "Default")
      (node (ref "J6") (pin "4") (pinfunction "4_4") (pintype "passive"))
    )
    (net (code "89") (name "unconnected-(J7-Pad1)") (class "Default")
      (node (ref "J7") (pin "1") (pinfunction "1_1") (pintype "passive"))
    )
    (net (code "90") (name "unconnected-(J7-Pad13)") (class "Default")
      (node (ref "J7") (pin "13") (pinfunction "13_13") (pintype "passive"))
    )
    (net (code "91") (name "unconnected-(J7-Pad17)") (class "Default")
      (node (ref "J7") (pin "17") (pinfunction "17_17") (pintype "passive"))
    )
    (net (code "92") (name "unconnected-(J7-Pad18)") (class "Default")
      (node (ref "J7") (pin "18") (pinfunction "18_18") (pintype "passive"))
    )
    (net (code "93") (name "unconnected-(J7-Pad19)") (class "Default")
      (node (ref "J7") (pin "19") (pinfunction "19_19") (pintype "passive"))
    )
    (net (code "94") (name "unconnected-(J9-Pad2)") (class "Default")
      (node (ref "J9") (pin "2") (pinfunction "2_2") (pintype "passive+no_connect"))
    )
    (net (code "95") (name "unconnected-(J9-Pad3)") (class "Default")
      (node (ref "J9") (pin "3") (pinfunction "3_3") (pintype "passive+no_connect"))
    )
    (net (code "96") (name "unconnected-(J9-Pad4)") (class "Default")
      (node (ref "J9") (pin "4") (pinfunction "4_4") (pintype "passive+no_connect"))
    )
    (net (code "97") (name "unconnected-(J9-Pad5)") (class "Default")
      (node (ref "J9") (pin "5") (pinfunction "5_5") (pintype "passive+no_connect"))
    )
    (net (code "98") (name "unconnected-(J9-Pad6)") (class "Default")
      (node (ref "J9") (pin "6") (pinfunction "6_6") (pintype "passive+no_connect"))
    )
    (net (code "99") (name "unconnected-(J9-Pad7)") (class "Default")
      (node (ref "J9") (pin "7") (pinfunction "7_7") (pintype "passive+no_connect"))
    )
    (net (code "100") (name "unconnected-(J9-Pad8)") (class "Default")
      (node (ref "J9") (pin "8") (pinfunction "8_8") (pintype "passive+no_connect"))
    )
    (net (code "101") (name "unconnected-(J10-Pad1)") (class "Default")
      (node (ref "J10") (pin "1") (pinfunction "1_1") (pintype "passive"))
    )
    (net (code "102") (name "unconnected-(J10-Pad5)") (class "Default")
      (node (ref "J10") (pin "5") (pinfunction "5_5") (pintype "passive"))
    )
    (net (code "103") (name "unconnected-(U2-PG-Pad3)") (class "Default")
      (node (ref "U2") (pin "3") (pinfunction "PG_3") (pintype "open_collector"))
    )
  )
)
